# 6_RS232_Debug.net
KiCad netlist of a schematic drawn in Altium Designer
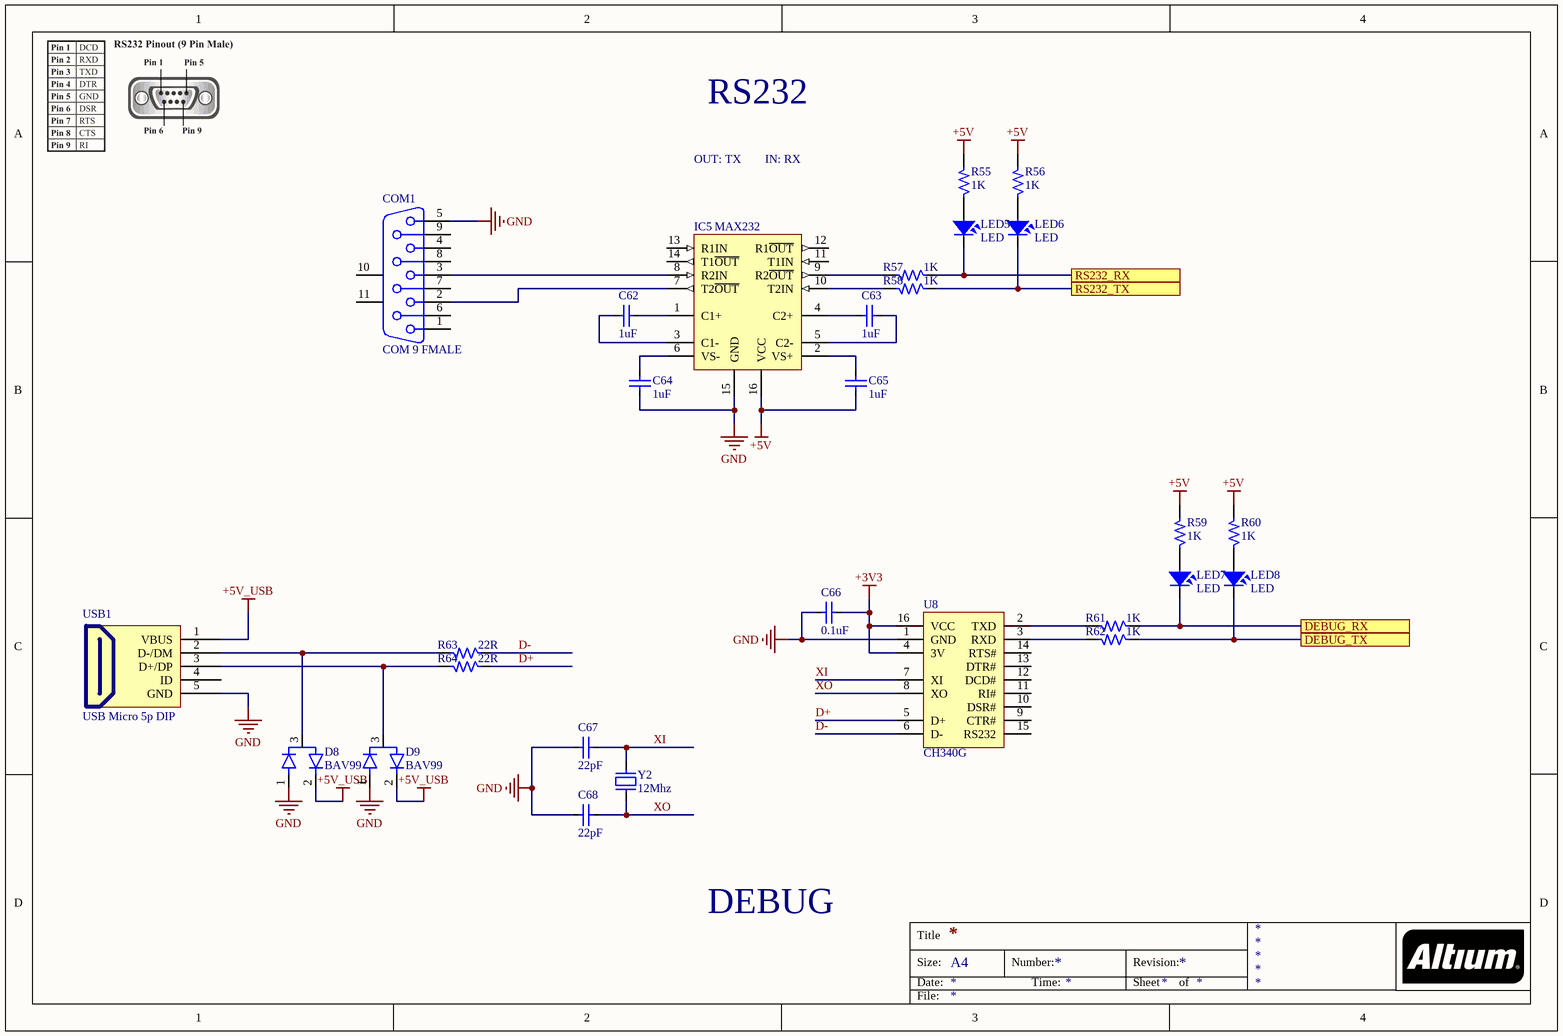
[diagram p0: [6]RS232_Debug.SchDoc]

(export (version "E")
  (design (tool "Eeschema 10.0.6"))
  (components
    (comp (ref "C62")
      (value "1uF")
      (footprint "CAP_0805")
      (description "Capacitor")
      (fields (field (name "PUBLISHER") "Altium Limited"))
      (libsource (lib "My Library") (part "CapSMD"))
    )
    (comp (ref "C63")
      (value "1uF")
      (footprint "CAP_0805")
      (description "Capacitor")
      (fields (field (name "PUBLISHER") "Altium Limited"))
      (libsource (lib "My Library") (part "CapSMD"))
    )
    (comp (ref "C64")
      (value "1uF")
      (footprint "CAP_0805")
      (description "Capacitor")
      (fields (field (name "PUBLISHER") "Altium Limited"))
      (libsource (lib "My Library") (part "CapSMD"))
    )
    (comp (ref "C65")
      (value "1uF")
      (footprint "CAP_0805")
      (description "Capacitor")
      (fields (field (name "PUBLISHER") "Altium Limited"))
      (libsource (lib "My Library") (part "CapSMD"))
    )
    (comp (ref "C66")
      (value "0.1uF")
      (footprint "CAP_0805")
      (description "Capacitor")
      (fields (field (name "PUBLISHER") "Altium Limited"))
      (libsource (lib "My Library") (part "CapSMD"))
    )
    (comp (ref "C67")
      (value "22pF")
      (footprint "CAP_0805")
      (description "Capacitor")
      (fields (field (name "PUBLISHER") "Altium Limited"))
      (libsource (lib "My Library") (part "CapSMD"))
    )
    (comp (ref "C68")
      (value "22pF")
      (footprint "CAP_0805")
      (description "Capacitor")
      (fields (field (name "PUBLISHER") "Altium Limited"))
      (libsource (lib "My Library") (part "CapSMD"))
    )
    (comp (ref "COM1")
      (value "COM 9 FMALE")
      (footprint "DSB 9-F")
      (description "COM 9")
      (fields (field (name "PUBLISHER") "Altium Limited"))
      (libsource (lib "syhaunguyen") (part "DSB9F"))
    )
    (comp (ref "D8")
      (value "BAV99")
      (footprint "DIO_BAV99")
      (fields (field (name "MF") "ON Semiconductor"))
      (libsource (lib "BAV99") (part "BAV99"))
    )
    (comp (ref "D9")
      (value "BAV99")
      (footprint "DIO_BAV99")
      (fields (field (name "MF") "ON Semiconductor"))
      (libsource (lib "BAV99") (part "BAV99"))
    )
    (comp (ref "IC5")
      (value "MAX232")
      (footprint "MAX232DR")
      (description "Dual EIA-232 Driver/Receiver")
      (libsource (lib "My Library") (part "MAX232"))
    )
    (comp (ref "LED5")
      (value "LED")
      (footprint "LED-0805-Blue")
      (description "LED Single colour Green and Red")
      (libsource (lib "My Library") (part "LED"))
    )
    (comp (ref "LED6")
      (value "LED")
      (footprint "LED-0805-Blue")
      (description "LED Single colour Green and Red")
      (libsource (lib "My Library") (part "LED"))
    )
    (comp (ref "LED7")
      (value "LED")
      (footprint "LED-0805-Blue")
      (description "LED Single colour Green and Red")
      (libsource (lib "My Library") (part "LED"))
    )
    (comp (ref "LED8")
      (value "LED")
      (footprint "LED-0805-Blue")
      (description "LED Single colour Green and Red")
      (libsource (lib "My Library") (part "LED"))
    )
    (comp (ref "R55")
      (value "1K")
      (footprint "R0805")
      (description "Resistor SMD")
      (libsource (lib "GPS_Traking_V1_1") (part "RM"))
    )
    (comp (ref "R56")
      (value "1K")
      (footprint "R0805")
      (description "Resistor SMD")
      (libsource (lib "GPS_Traking_V1_1") (part "RM"))
    )
    (comp (ref "R57")
      (value "1K")
      (footprint "R0805")
      (description "Resistor SMD")
      (libsource (lib "GPS_Traking_V1_1") (part "RM"))
    )
    (comp (ref "R58")
      (value "1K")
      (footprint "R0805")
      (description "Resistor SMD")
      (libsource (lib "GPS_Traking_V1_1") (part "RM"))
    )
    (comp (ref "R59")
      (value "1K")
      (footprint "R0805")
      (description "Resistor SMD")
      (libsource (lib "GPS_Traking_V1_1") (part "RM"))
    )
    (comp (ref "R60")
      (value "1K")
      (footprint "R0805")
      (description "Resistor SMD")
      (libsource (lib "GPS_Traking_V1_1") (part "RM"))
    )
    (comp (ref "R61")
      (value "1K")
      (footprint "R0805")
      (description "Resistor SMD")
      (libsource (lib "GPS_Traking_V1_1") (part "RM"))
    )
    (comp (ref "R62")
      (value "1K")
      (footprint "R0805")
      (description "Resistor SMD")
      (libsource (lib "GPS_Traking_V1_1") (part "RM"))
    )
    (comp (ref "R63")
      (value "22R")
      (footprint "R0805")
      (description "Resistor SMD")
      (libsource (lib "GPS_Traking_V1_1") (part "RM"))
    )
    (comp (ref "R64")
      (value "22R")
      (footprint "R0805")
      (description "Resistor SMD")
      (libsource (lib "GPS_Traking_V1_1") (part "RM"))
    )
    (comp (ref "U8")
      (value "CH340G")
      (footprint "SO16")
      (description "High and Low Side Driver")
      (fields (field (name "PUBLISHER") "Altium Limited"))
      (libsource (lib "My Library") (part "CH340G"))
    )
    (comp (ref "USB1")
      (value "USB Micro 5p DIP")
      (footprint "USB Micro 5p DIP")
      (description "USB Type B")
      (libsource (lib "Altium_Lib_by_KhueNguyenCreator") (part "USB Micro 5p DIP"))
    )
    (comp (ref "Y2")
      (value "12Mhz")
      (footprint "Thach Anh 2 chan SMD5032")
      (description "Crystal For all Crystal 2pin.")
      (libsource (lib "Altium_Lib_by_KhueNguyenCreator") (part "Thach Anh 2 chan SMD 5032"))
    )
  )
  (nets
    (net (code "1") (name "+3V3") (class "Default")
      (node (ref "C66") (pin "1") (pinfunction "1_1") (pintype "passive"))
      (node (ref "U8") (pin "16") (pinfunction "VCC_16") (pintype "passive"))
      (node (ref "U8") (pin "4") (pinfunction "3V_4") (pintype "passive"))
    )
    (net (code "2") (name "+5V") (class "Default")
      (node (ref "C65") (pin "2") (pinfunction "2_2") (pintype "passive"))
      (node (ref "IC5") (pin "16") (pinfunction "VCC_16") (pintype "power_in"))
      (node (ref "R55") (pin "2") (pinfunction "2_2") (pintype "passive"))
      (node (ref "R56") (pin "2") (pinfunction "2_2") (pintype "passive"))
      (node (ref "R59") (pin "2") (pinfunction "2_2") (pintype "passive"))
      (node (ref "R60") (pin "2") (pinfunction "2_2") (pintype "passive"))
    )
    (net (code "3") (name "+5V_USB") (class "Default")
      (node (ref "D8") (pin "2") (pinfunction "2_2") (pintype "passive"))
      (node (ref "D9") (pin "2") (pinfunction "2_2") (pintype "passive"))
      (node (ref "USB1") (pin "1") (pinfunction "VBUS_1") (pintype "passive"))
    )
    (net (code "4") (name "/D+") (class "Default")
      (node (ref "R64") (pin "1") (pinfunction "1_1") (pintype "passive"))
      (node (ref "U8") (pin "5") (pinfunction "D+_5") (pintype "passive"))
    )
    (net (code "5") (name "/D-") (class "Default")
      (node (ref "R63") (pin "1") (pinfunction "1_1") (pintype "passive"))
      (node (ref "U8") (pin "6") (pinfunction "D-_6") (pintype "passive"))
    )
    (net (code "6") (name "/DEBUG_RX") (class "Default")
      (node (ref "LED7") (pin "2") (pinfunction "2_2") (pintype "passive"))
      (node (ref "R61") (pin "1") (pinfunction "1_1") (pintype "passive"))
    )
    (net (code "7") (name "/DEBUG_TX") (class "Default")
      (node (ref "LED8") (pin "2") (pinfunction "2_2") (pintype "passive"))
      (node (ref "R62") (pin "1") (pinfunction "1_1") (pintype "passive"))
    )
    (net (code "8") (name "/RS232_RX") (class "Default")
      (node (ref "LED5") (pin "2") (pinfunction "2_2") (pintype "passive"))
      (node (ref "R57") (pin "1") (pinfunction "1_1") (pintype "passive"))
    )
    (net (code "9") (name "/RS232_TX") (class "Default")
      (node (ref "LED6") (pin "2") (pinfunction "2_2") (pintype "passive"))
      (node (ref "R58") (pin "1") (pinfunction "1_1") (pintype "passive"))
    )
    (net (code "10") (name "/XI") (class "Default")
      (node (ref "C67") (pin "1") (pinfunction "1_1") (pintype "passive"))
      (node (ref "U8") (pin "7") (pinfunction "XI_7") (pintype "passive"))
      (node (ref "Y2") (pin "1") (pinfunction "1_1") (pintype "passive"))
    )
    (net (code "11") (name "/XO") (class "Default")
      (node (ref "C68") (pin "1") (pinfunction "1_1") (pintype "passive"))
      (node (ref "U8") (pin "8") (pinfunction "XO_8") (pintype "passive"))
      (node (ref "Y2") (pin "2") (pinfunction "2_2") (pintype "passive"))
    )
    (net (code "12") (name "GND") (class "Default")
      (node (ref "C64") (pin "2") (pinfunction "2_2") (pintype "passive"))
      (node (ref "C66") (pin "2") (pinfunction "2_2") (pintype "passive"))
      (node (ref "C67") (pin "2") (pinfunction "2_2") (pintype "passive"))
      (node (ref "C68") (pin "2") (pinfunction "2_2") (pintype "passive"))
      (node (ref "COM1") (pin "5") (pinfunction "5_5") (pintype "passive"))
      (node (ref "D8") (pin "1") (pinfunction "1_1") (pintype "passive"))
      (node (ref "D9") (pin "1") (pinfunction "1_1") (pintype "passive"))
      (node (ref "IC5") (pin "15") (pinfunction "GND_15") (pintype "power_in"))
      (node (ref "U8") (pin "1") (pinfunction "GND_1") (pintype "passive"))
      (node (ref "USB1") (pin "5") (pinfunction "GND_5") (pintype "passive"))
    )
    (net (code "13") (name "Net-(IC5-C1+)") (class "Default")
      (node (ref "C62") (pin "1") (pinfunction "1_1") (pintype "passive"))
      (node (ref "IC5") (pin "1") (pinfunction "C1+_1") (pintype "passive"))
    )
    (net (code "14") (name "Net-(IC5-C1-)") (class "Default")
      (node (ref "C62") (pin "2") (pinfunction "2_2") (pintype "passive"))
      (node (ref "IC5") (pin "3") (pinfunction "C1-_3") (pintype "passive"))
    )
    (net (code "15") (name "Net-(IC5-C2+)") (class "Default")
      (node (ref "C63") (pin "2") (pinfunction "2_2") (pintype "passive"))
      (node (ref "IC5") (pin "4") (pinfunction "C2+_4") (pintype "passive"))
    )
    (net (code "16") (name "Net-(IC5-C2-)") (class "Default")
      (node (ref "C63") (pin "1") (pinfunction "1_1") (pintype "passive"))
      (node (ref "IC5") (pin "5") (pinfunction "C2-_5") (pintype "passive"))
    )
    (net (code "17") (name "Net-(IC5-R2IN)") (class "Default")
      (node (ref "COM1") (pin "3") (pinfunction "3_3") (pintype "passive"))
      (node (ref "IC5") (pin "8") (pinfunction "R2IN_8") (pintype "input"))
    )
    (net (code "18") (name "Net-(IC5-R2~{OUT})") (class "Default")
      (node (ref "IC5") (pin "9") (pinfunction "R2~{OUT}_9") (pintype "output"))
      (node (ref "R57") (pin "2") (pinfunction "2_2") (pintype "passive"))
    )
    (net (code "19") (name "Net-(IC5-T2IN)") (class "Default")
      (node (ref "IC5") (pin "10") (pinfunction "T2IN_10") (pintype "input"))
      (node (ref "R58") (pin "2") (pinfunction "2_2") (pintype "passive"))
    )
    (net (code "20") (name "Net-(IC5-T2~{OUT})") (class "Default")
      (node (ref "COM1") (pin "2") (pinfunction "2_2") (pintype "passive"))
      (node (ref "IC5") (pin "7") (pinfunction "T2~{OUT}_7") (pintype "output"))
    )
    (net (code "21") (name "Net-(IC5-VS+)") (class "Default")
      (node (ref "C65") (pin "1") (pinfunction "1_1") (pintype "passive"))
      (node (ref "IC5") (pin "2") (pinfunction "VS+_2") (pintype "power_in"))
    )
    (net (code "22") (name "Net-(IC5-VS-)") (class "Default")
      (node (ref "C64") (pin "1") (pinfunction "1_1") (pintype "passive"))
      (node (ref "IC5") (pin "6") (pinfunction "VS-_6") (pintype "power_in"))
    )
    (net (code "23") (name "Net-(LED5-Pad1)") (class "Default")
      (node (ref "LED5") (pin "1") (pinfunction "1_1") (pintype "passive"))
      (node (ref "R55") (pin "1") (pinfunction "1_1") (pintype "passive"))
    )
    (net (code "24") (name "Net-(LED6-Pad1)") (class "Default")
      (node (ref "LED6") (pin "1") (pinfunction "1_1") (pintype "passive"))
      (node (ref "R56") (pin "1") (pinfunction "1_1") (pintype "passive"))
    )
    (net (code "25") (name "Net-(LED7-Pad1)") (class "Default")
      (node (ref "LED7") (pin "1") (pinfunction "1_1") (pintype "passive"))
      (node (ref "R59") (pin "1") (pinfunction "1_1") (pintype "passive"))
    )
    (net (code "26") (name "Net-(LED8-Pad1)") (class "Default")
      (node (ref "LED8") (pin "1") (pinfunction "1_1") (pintype "passive"))
      (node (ref "R60") (pin "1") (pinfunction "1_1") (pintype "passive"))
    )
    (net (code "27") (name "Net-(U8-RXD)") (class "Default")
      (node (ref "R62") (pin "2") (pinfunction "2_2") (pintype "passive"))
      (node (ref "U8") (pin "3") (pinfunction "RXD_3") (pintype "passive"))
    )
    (net (code "28") (name "Net-(U8-TXD)") (class "Default")
      (node (ref "R61") (pin "2") (pinfunction "2_2") (pintype "passive"))
      (node (ref "U8") (pin "2") (pinfunction "TXD_2") (pintype "passive"))
    )
    (net (code "29") (name "Net-(USB1-D+{slash}DP)") (class "Default")
      (node (ref "D9") (pin "3") (pinfunction "3_3") (pintype "passive"))
      (node (ref "R64") (pin "2") (pinfunction "2_2") (pintype "passive"))
      (node (ref "USB1") (pin "3") (pinfunction "D+/DP_3") (pintype "passive"))
    )
    (net (code "30") (name "Net-(USB1-D-{slash}DM)") (class "Default")
      (node (ref "D8") (pin "3") (pinfunction "3_3") (pintype "passive"))
      (node (ref "R63") (pin "2") (pinfunction "2_2") (pintype "passive"))
      (node (ref "USB1") (pin "2") (pinfunction "D-/DM_2") (pintype "passive"))
    )
    (net (code "31") (name "unconnected-(COM1-MH1-Pad10)") (class "Default")
      (node (ref "COM1") (pin "10") (pinfunction "MH1_10") (pintype "passive"))
    )
    (net (code "32") (name "unconnected-(COM1-MH2-Pad11)") (class "Default")
      (node (ref "COM1") (pin "11") (pinfunction "MH2_11") (pintype "passive"))
    )
    (net (code "33") (name "unconnected-(COM1-Pad1)") (class "Default")
      (node (ref "COM1") (pin "1") (pinfunction "1_1") (pintype "passive"))
    )
    (net (code "34") (name "unconnected-(COM1-Pad4)") (class "Default")
      (node (ref "COM1") (pin "4") (pinfunction "4_4") (pintype "passive"))
    )
    (net (code "35") (name "unconnected-(COM1-Pad6)") (class "Default")
      (node (ref "COM1") (pin "6") (pinfunction "6_6") (pintype "passive"))
    )
    (net (code "36") (name "unconnected-(COM1-Pad7)") (class "Default")
      (node (ref "COM1") (pin "7") (pinfunction "7_7") (pintype "passive"))
    )
    (net (code "37") (name "unconnected-(COM1-Pad8)") (class "Default")
      (node (ref "COM1") (pin "8") (pinfunction "8_8") (pintype "passive"))
    )
    (net (code "38") (name "unconnected-(COM1-Pad9)") (class "Default")
      (node (ref "COM1") (pin "9") (pinfunction "9_9") (pintype "passive"))
    )
    (net (code "39") (name "unconnected-(IC5-R1IN-Pad13)") (class "Default")
      (node (ref "IC5") (pin "13") (pinfunction "R1IN_13") (pintype "input"))
    )
    (net (code "40") (name "unconnected-(IC5-R1~{OUT}-Pad12)") (class "Default")
      (node (ref "IC5") (pin "12") (pinfunction "R1~{OUT}_12") (pintype "output"))
    )
    (net (code "41") (name "unconnected-(IC5-T1IN-Pad11)") (class "Default")
      (node (ref "IC5") (pin "11") (pinfunction "T1IN_11") (pintype "input"))
    )
    (net (code "42") (name "unconnected-(IC5-T1~{OUT}-Pad14)") (class "Default")
      (node (ref "IC5") (pin "14") (pinfunction "T1~{OUT}_14") (pintype "output"))
    )
    (net (code "43") (name "unconnected-(U8-CTR#-Pad9)") (class "Default")
      (node (ref "U8") (pin "9") (pinfunction "CTR#_9") (pintype "passive"))
    )
    (net (code "44") (name "unconnected-(U8-DCD#-Pad12)") (class "Default")
      (node (ref "U8") (pin "12") (pinfunction "DCD#_12") (pintype "passive"))
    )
    (net (code "45") (name "unconnected-(U8-DSR#-Pad10)") (class "Default")
      (node (ref "U8") (pin "10") (pinfunction "DSR#_10") (pintype "passive"))
    )
    (net (code "46") (name "unconnected-(U8-DTR#-Pad13)") (class "Default")
      (node (ref "U8") (pin "13") (pinfunction "DTR#_13") (pintype "passive"))
    )
    (net (code "47") (name "unconnected-(U8-RI#-Pad11)") (class "Default")
      (node (ref "U8") (pin "11") (pinfunction "RI#_11") (pintype "passive"))
    )
    (net (code "48") (name "unconnected-(U8-RS232-Pad15)") (class "Default")
      (node (ref "U8") (pin "15") (pinfunction "RS232_15") (pintype "passive"))
    )
    (net (code "49") (name "unconnected-(U8-RTS#-Pad14)") (class "Default")
      (node (ref "U8") (pin "14") (pinfunction "RTS#_14") (pintype "passive"))
    )
    (net (code "50") (name "unconnected-(USB1-ID-Pad4)") (class "Default")
      (node (ref "USB1") (pin "4") (pinfunction "ID_4") (pintype "passive"))
    )
  )
)
